# fastkey_-_v1.net
KiCad netlist of a schematic drawn in EAGLE
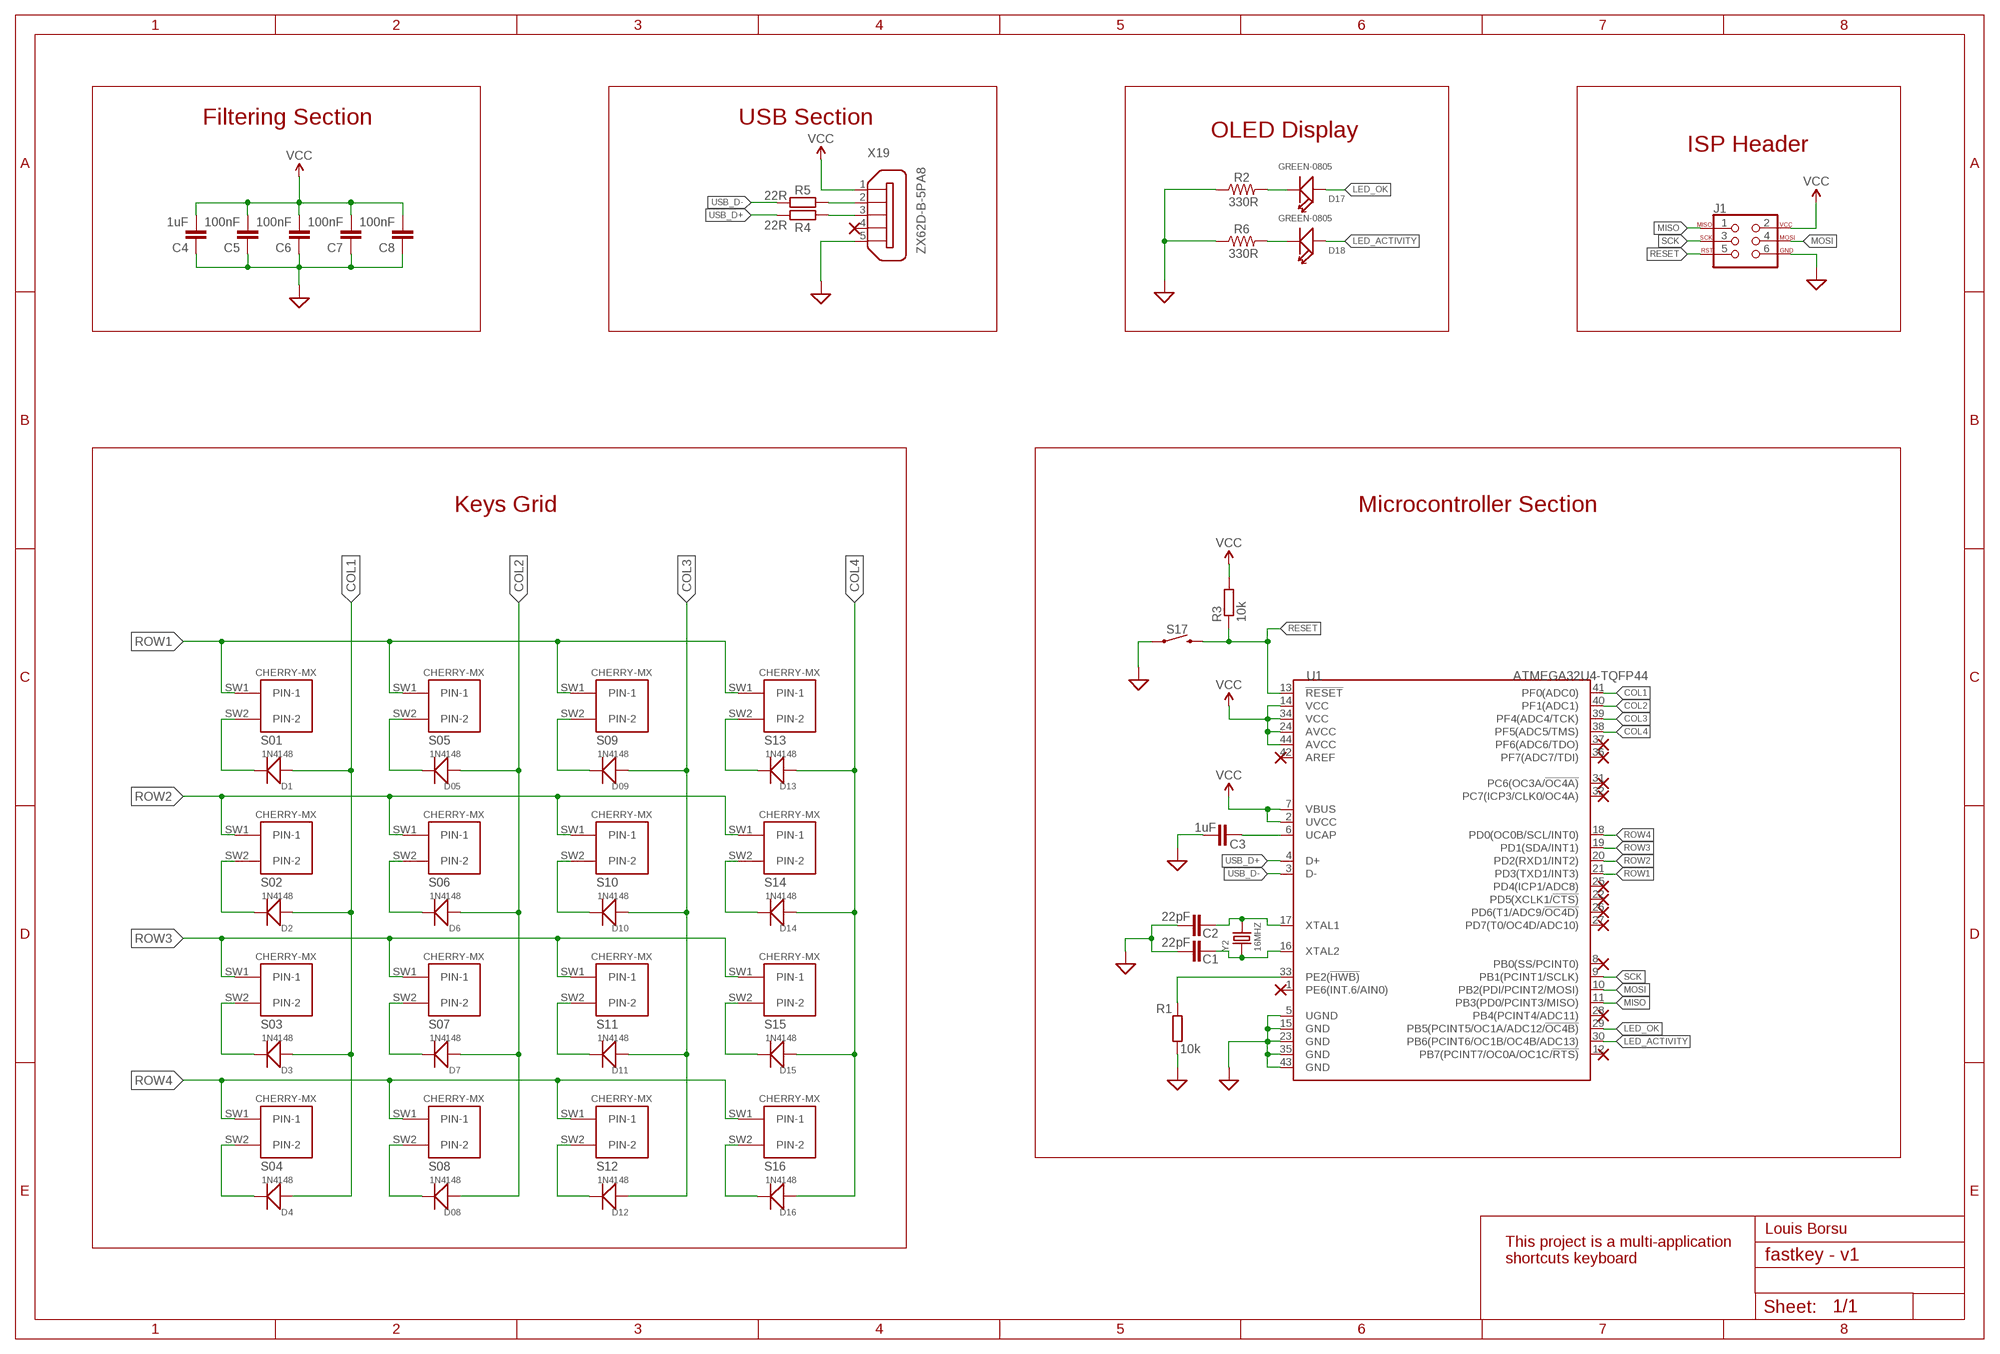
[diagram p0: schematic, sheet 1]

(export (version "E")
  (design (tool "Eeschema 10.0.6"))
  (components
    (comp (ref "C1")
      (value "22pF")
      (footprint "eagle-import:RESC0805_M")
      (libsource (lib "eagle-import") (part "CAPACITOR_0805_M"))
    )
    (comp (ref "C2")
      (value "22pF")
      (footprint "eagle-import:RESC0805_M")
      (libsource (lib "eagle-import") (part "CAPACITOR_0805_M"))
    )
    (comp (ref "C3")
      (value "1uF")
      (footprint "eagle-import:RESC0805_M")
      (libsource (lib "eagle-import") (part "CAPACITOR_0805_M"))
    )
    (comp (ref "C4")
      (value "1uF")
      (footprint "eagle-import:RESC0805_M")
      (libsource (lib "eagle-import") (part "CAPACITOR_0805_M"))
    )
    (comp (ref "C5")
      (value "100nF")
      (footprint "eagle-import:RESC0805_M")
      (libsource (lib "eagle-import") (part "CAPACITOR_0805_M"))
    )
    (comp (ref "C6")
      (value "100nF")
      (footprint "eagle-import:RESC0805_M")
      (libsource (lib "eagle-import") (part "CAPACITOR_0805_M"))
    )
    (comp (ref "C7")
      (value "100nF")
      (footprint "eagle-import:RESC0805_M")
      (libsource (lib "eagle-import") (part "CAPACITOR_0805_M"))
    )
    (comp (ref "C8")
      (value "100nF")
      (footprint "eagle-import:RESC0805_M")
      (libsource (lib "eagle-import") (part "CAPACITOR_0805_M"))
    )
    (comp (ref "D1")
      (value "1N4148")
      (footprint "eagle-import:LL-34")
      (libsource (lib "eagle-import") (part "SMD-DIODE-SWITCH-1N4148(LL-34)"))
    )
    (comp (ref "D2")
      (value "1N4148")
      (footprint "eagle-import:LL-34")
      (libsource (lib "eagle-import") (part "SMD-DIODE-SWITCH-1N4148(LL-34)"))
    )
    (comp (ref "D3")
      (value "1N4148")
      (footprint "eagle-import:LL-34")
      (libsource (lib "eagle-import") (part "SMD-DIODE-SWITCH-1N4148(LL-34)"))
    )
    (comp (ref "D4")
      (value "1N4148")
      (footprint "eagle-import:LL-34")
      (libsource (lib "eagle-import") (part "SMD-DIODE-SWITCH-1N4148(LL-34)"))
    )
    (comp (ref "D05")
      (value "1N4148")
      (footprint "eagle-import:LL-34")
      (libsource (lib "eagle-import") (part "SMD-DIODE-SWITCH-1N4148(LL-34)"))
    )
    (comp (ref "D6")
      (value "1N4148")
      (footprint "eagle-import:LL-34")
      (libsource (lib "eagle-import") (part "SMD-DIODE-SWITCH-1N4148(LL-34)"))
    )
    (comp (ref "D7")
      (value "1N4148")
      (footprint "eagle-import:LL-34")
      (libsource (lib "eagle-import") (part "SMD-DIODE-SWITCH-1N4148(LL-34)"))
    )
    (comp (ref "D08")
      (value "1N4148")
      (footprint "eagle-import:LL-34")
      (libsource (lib "eagle-import") (part "SMD-DIODE-SWITCH-1N4148(LL-34)"))
    )
    (comp (ref "D09")
      (value "1N4148")
      (footprint "eagle-import:LL-34")
      (libsource (lib "eagle-import") (part "SMD-DIODE-SWITCH-1N4148(LL-34)"))
    )
    (comp (ref "D10")
      (value "1N4148")
      (footprint "eagle-import:LL-34")
      (libsource (lib "eagle-import") (part "SMD-DIODE-SWITCH-1N4148(LL-34)"))
    )
    (comp (ref "D11")
      (value "1N4148")
      (footprint "eagle-import:LL-34")
      (libsource (lib "eagle-import") (part "SMD-DIODE-SWITCH-1N4148(LL-34)"))
    )
    (comp (ref "D12")
      (value "1N4148")
      (footprint "eagle-import:LL-34")
      (libsource (lib "eagle-import") (part "SMD-DIODE-SWITCH-1N4148(LL-34)"))
    )
    (comp (ref "D13")
      (value "1N4148")
      (footprint "eagle-import:LL-34")
      (libsource (lib "eagle-import") (part "SMD-DIODE-SWITCH-1N4148(LL-34)"))
    )
    (comp (ref "D14")
      (value "1N4148")
      (footprint "eagle-import:LL-34")
      (libsource (lib "eagle-import") (part "SMD-DIODE-SWITCH-1N4148(LL-34)"))
    )
    (comp (ref "D15")
      (value "1N4148")
      (footprint "eagle-import:LL-34")
      (libsource (lib "eagle-import") (part "SMD-DIODE-SWITCH-1N4148(LL-34)"))
    )
    (comp (ref "D16")
      (value "1N4148")
      (footprint "eagle-import:LL-34")
      (libsource (lib "eagle-import") (part "SMD-DIODE-SWITCH-1N4148(LL-34)"))
    )
    (comp (ref "D17")
      (value "GREEN-0805")
      (footprint "eagle-import:LED-0805")
      (fields (field (name "MPN") "17-215SYGC/S530-E2/TR8"))
      (libsource (lib "eagle-import") (part "SMD-LED-CLEAR-GREEN(0805)"))
    )
    (comp (ref "D18")
      (value "GREEN-0805")
      (footprint "eagle-import:LED-0805")
      (fields (field (name "MPN") "17-215SYGC/S530-E2/TR8"))
      (libsource (lib "eagle-import") (part "SMD-LED-CLEAR-GREEN(0805)"))
    )
    (comp (ref "J1")
      (value "AVR_SPI_PROG_3X22X3_LOCK")
      (footprint "eagle-import:2X3_LOCK")
      (libsource (lib "eagle-import") (part "AVR_SPI_PROG_3X22X3_LOCK"))
    )
    (comp (ref "R1")
      (value "10k")
      (footprint "eagle-import:R0805")
      (libsource (lib "eagle-import") (part "R-EU_R0805"))
    )
    (comp (ref "R2")
      (value "330R")
      (footprint "eagle-import:0805")
      (libsource (lib "eagle-import") (part "RESISTOR0805"))
    )
    (comp (ref "R3")
      (value "10k")
      (footprint "eagle-import:R0805")
      (libsource (lib "eagle-import") (part "R-EU_R0805"))
    )
    (comp (ref "R4")
      (value "22R")
      (footprint "eagle-import:R0805")
      (libsource (lib "eagle-import") (part "R-EU_R0805"))
    )
    (comp (ref "R5")
      (value "22R")
      (footprint "eagle-import:R0805")
      (libsource (lib "eagle-import") (part "R-EU_R0805"))
    )
    (comp (ref "R6")
      (value "330R")
      (footprint "eagle-import:0805")
      (libsource (lib "eagle-import") (part "RESISTOR0805"))
    )
    (comp (ref "S01")
      (value "CHERRY-MX")
      (footprint "eagle-import:CHERRY-MX")
      (libsource (lib "eagle-import") (part "CHERRY-MX"))
    )
    (comp (ref "S02")
      (value "CHERRY-MX")
      (footprint "eagle-import:CHERRY-MX")
      (libsource (lib "eagle-import") (part "CHERRY-MX"))
    )
    (comp (ref "S03")
      (value "CHERRY-MX")
      (footprint "eagle-import:CHERRY-MX")
      (libsource (lib "eagle-import") (part "CHERRY-MX"))
    )
    (comp (ref "S04")
      (value "CHERRY-MX")
      (footprint "eagle-import:CHERRY-MX")
      (libsource (lib "eagle-import") (part "CHERRY-MX"))
    )
    (comp (ref "S05")
      (value "CHERRY-MX")
      (footprint "eagle-import:CHERRY-MX")
      (libsource (lib "eagle-import") (part "CHERRY-MX"))
    )
    (comp (ref "S06")
      (value "CHERRY-MX")
      (footprint "eagle-import:CHERRY-MX")
      (libsource (lib "eagle-import") (part "CHERRY-MX"))
    )
    (comp (ref "S07")
      (value "CHERRY-MX")
      (footprint "eagle-import:CHERRY-MX")
      (libsource (lib "eagle-import") (part "CHERRY-MX"))
    )
    (comp (ref "S08")
      (value "CHERRY-MX")
      (footprint "eagle-import:CHERRY-MX")
      (libsource (lib "eagle-import") (part "CHERRY-MX"))
    )
    (comp (ref "S09")
      (value "CHERRY-MX")
      (footprint "eagle-import:CHERRY-MX")
      (libsource (lib "eagle-import") (part "CHERRY-MX"))
    )
    (comp (ref "S10")
      (value "CHERRY-MX")
      (footprint "eagle-import:CHERRY-MX")
      (libsource (lib "eagle-import") (part "CHERRY-MX"))
    )
    (comp (ref "S11")
      (value "CHERRY-MX")
      (footprint "eagle-import:CHERRY-MX")
      (libsource (lib "eagle-import") (part "CHERRY-MX"))
    )
    (comp (ref "S12")
      (value "CHERRY-MX")
      (footprint "eagle-import:CHERRY-MX")
      (libsource (lib "eagle-import") (part "CHERRY-MX"))
    )
    (comp (ref "S13")
      (value "CHERRY-MX")
      (footprint "eagle-import:CHERRY-MX")
      (libsource (lib "eagle-import") (part "CHERRY-MX"))
    )
    (comp (ref "S14")
      (value "CHERRY-MX")
      (footprint "eagle-import:CHERRY-MX")
      (libsource (lib "eagle-import") (part "CHERRY-MX"))
    )
    (comp (ref "S15")
      (value "CHERRY-MX")
      (footprint "eagle-import:CHERRY-MX")
      (libsource (lib "eagle-import") (part "CHERRY-MX"))
    )
    (comp (ref "S16")
      (value "CHERRY-MX")
      (footprint "eagle-import:CHERRY-MX")
      (libsource (lib "eagle-import") (part "CHERRY-MX"))
    )
    (comp (ref "S17")
      (value "MOMENTARY-SWITCH-SPST-SMD-6.2MM-TALL")
      (footprint "eagle-import:TACTILE_SWITCH_SMD_6.2MM_TALL")
      (libsource (lib "eagle-import") (part "MOMENTARY-SWITCH-SPST-SMD-6.2MM-TALL"))
    )
    (comp (ref "U1")
      (value "ATMEGA32U4-TQFP44")
      (footprint "eagle-import:TQFP44-0.8-9.6X9.6MM")
      (fields (field (name "MPN") "ATMEGA32U4"))
      (libsource (lib "eagle-import") (part "MCU-ATMEGA32U4-AU(TQFP44)"))
    )
    (comp (ref "X19")
      (value "ZX62D-B-5PA8")
      (footprint "eagle-import:ZX62D-B-5PA8")
      (fields (field (name "MF") "Hirose"))
      (libsource (lib "eagle-import") (part "ZX62D-B-5PA8"))
    )
    (comp (ref "Y2")
      (value "16MHZ")
      (footprint "eagle-import:X2-SMD-5.0X3.2X1.3MM")
      (fields (field (name "MPN") "X053201602002"))
      (libsource (lib "eagle-import") (part "SMD-CRYSTAL-16MHZ-8PF-20PPM-40R(2P-5.0X3.2MM)"))
    )
  )
  (nets
    (net (code "1") (name "COL1") (class "Default")
      (node (ref "D1") (pin "A") (pinfunction "+_A") (pintype "passive"))
      (node (ref "D2") (pin "A") (pinfunction "+_A") (pintype "passive"))
      (node (ref "D3") (pin "A") (pinfunction "+_A") (pintype "passive"))
      (node (ref "D4") (pin "A") (pinfunction "+_A") (pintype "passive"))
      (node (ref "U1") (pin "41") (pinfunction "PF0(ADC0)_41") (pintype "bidirectional"))
    )
    (net (code "2") (name "COL2") (class "Default")
      (node (ref "D05") (pin "A") (pinfunction "+_A") (pintype "passive"))
      (node (ref "D08") (pin "A") (pinfunction "+_A") (pintype "passive"))
      (node (ref "D6") (pin "A") (pinfunction "+_A") (pintype "passive"))
      (node (ref "D7") (pin "A") (pinfunction "+_A") (pintype "passive"))
      (node (ref "U1") (pin "40") (pinfunction "PF1(ADC1)_40") (pintype "bidirectional"))
    )
    (net (code "3") (name "COL3") (class "Default")
      (node (ref "D09") (pin "A") (pinfunction "+_A") (pintype "passive"))
      (node (ref "D10") (pin "A") (pinfunction "+_A") (pintype "passive"))
      (node (ref "D11") (pin "A") (pinfunction "+_A") (pintype "passive"))
      (node (ref "D12") (pin "A") (pinfunction "+_A") (pintype "passive"))
      (node (ref "U1") (pin "39") (pinfunction "PF4(ADC4/TCK)_39") (pintype "bidirectional"))
    )
    (net (code "4") (name "COL4") (class "Default")
      (node (ref "D13") (pin "A") (pinfunction "+_A") (pintype "passive"))
      (node (ref "D14") (pin "A") (pinfunction "+_A") (pintype "passive"))
      (node (ref "D15") (pin "A") (pinfunction "+_A") (pintype "passive"))
      (node (ref "D16") (pin "A") (pinfunction "+_A") (pintype "passive"))
      (node (ref "U1") (pin "38") (pinfunction "PF5(ADC5/TMS)_38") (pintype "bidirectional"))
    )
    (net (code "5") (name "LED_ACTIVITY") (class "Default")
      (node (ref "D18") (pin "+") (pinfunction "+_+") (pintype "passive"))
      (node (ref "U1") (pin "30") (pinfunction "PB6(PCINT6/OC1B/OC4B/ADC13)_30") (pintype "bidirectional"))
    )
    (net (code "6") (name "LED_OK") (class "Default")
      (node (ref "D17") (pin "+") (pinfunction "+_+") (pintype "passive"))
      (node (ref "U1") (pin "29") (pinfunction "PB5(PCINT5/OC1A/ADC12/~{OC4B})_29") (pintype "bidirectional"))
    )
    (net (code "7") (name "MISO") (class "Default")
      (node (ref "J1") (pin "1") (pinfunction "1_1") (pintype "passive"))
      (node (ref "U1") (pin "11") (pinfunction "PB3(PD0/PCINT3/MISO)_11") (pintype "bidirectional"))
    )
    (net (code "8") (name "MOSI") (class "Default")
      (node (ref "J1") (pin "4") (pinfunction "4_4") (pintype "passive"))
      (node (ref "U1") (pin "10") (pinfunction "PB2(PDI/PCINT2/MOSI)_10") (pintype "bidirectional"))
    )
    (net (code "9") (name "Net-(D1--)") (class "Default")
      (node (ref "D1") (pin "C") (pinfunction "-_C") (pintype "passive"))
      (node (ref "S01") (pin "SW2") (pinfunction "PIN-2_SW2") (pintype "bidirectional"))
    )
    (net (code "10") (name "Net-(D2--)") (class "Default")
      (node (ref "D2") (pin "C") (pinfunction "-_C") (pintype "passive"))
      (node (ref "S02") (pin "SW2") (pinfunction "PIN-2_SW2") (pintype "bidirectional"))
    )
    (net (code "11") (name "Net-(D3--)") (class "Default")
      (node (ref "D3") (pin "C") (pinfunction "-_C") (pintype "passive"))
      (node (ref "S03") (pin "SW2") (pinfunction "PIN-2_SW2") (pintype "bidirectional"))
    )
    (net (code "12") (name "Net-(D4--)") (class "Default")
      (node (ref "D4") (pin "C") (pinfunction "-_C") (pintype "passive"))
      (node (ref "S04") (pin "SW2") (pinfunction "PIN-2_SW2") (pintype "bidirectional"))
    )
    (net (code "13") (name "Net-(D05--)") (class "Default")
      (node (ref "D05") (pin "C") (pinfunction "-_C") (pintype "passive"))
      (node (ref "S05") (pin "SW2") (pinfunction "PIN-2_SW2") (pintype "bidirectional"))
    )
    (net (code "14") (name "Net-(D6--)") (class "Default")
      (node (ref "D6") (pin "C") (pinfunction "-_C") (pintype "passive"))
      (node (ref "S06") (pin "SW2") (pinfunction "PIN-2_SW2") (pintype "bidirectional"))
    )
    (net (code "15") (name "Net-(D7--)") (class "Default")
      (node (ref "D7") (pin "C") (pinfunction "-_C") (pintype "passive"))
      (node (ref "S07") (pin "SW2") (pinfunction "PIN-2_SW2") (pintype "bidirectional"))
    )
    (net (code "16") (name "Net-(D08--)") (class "Default")
      (node (ref "D08") (pin "C") (pinfunction "-_C") (pintype "passive"))
      (node (ref "S08") (pin "SW2") (pinfunction "PIN-2_SW2") (pintype "bidirectional"))
    )
    (net (code "17") (name "Net-(D09--)") (class "Default")
      (node (ref "D09") (pin "C") (pinfunction "-_C") (pintype "passive"))
      (node (ref "S09") (pin "SW2") (pinfunction "PIN-2_SW2") (pintype "bidirectional"))
    )
    (net (code "18") (name "Net-(D10--)") (class "Default")
      (node (ref "D10") (pin "C") (pinfunction "-_C") (pintype "passive"))
      (node (ref "S10") (pin "SW2") (pinfunction "PIN-2_SW2") (pintype "bidirectional"))
    )
    (net (code "19") (name "Net-(D11--)") (class "Default")
      (node (ref "D11") (pin "C") (pinfunction "-_C") (pintype "passive"))
      (node (ref "S11") (pin "SW2") (pinfunction "PIN-2_SW2") (pintype "bidirectional"))
    )
    (net (code "20") (name "Net-(D12--)") (class "Default")
      (node (ref "D12") (pin "C") (pinfunction "-_C") (pintype "passive"))
      (node (ref "S12") (pin "SW2") (pinfunction "PIN-2_SW2") (pintype "bidirectional"))
    )
    (net (code "21") (name "Net-(D13--)") (class "Default")
      (node (ref "D13") (pin "C") (pinfunction "-_C") (pintype "passive"))
      (node (ref "S13") (pin "SW2") (pinfunction "PIN-2_SW2") (pintype "bidirectional"))
    )
    (net (code "22") (name "Net-(D14--)") (class "Default")
      (node (ref "D14") (pin "C") (pinfunction "-_C") (pintype "passive"))
      (node (ref "S14") (pin "SW2") (pinfunction "PIN-2_SW2") (pintype "bidirectional"))
    )
    (net (code "23") (name "Net-(D15--)") (class "Default")
      (node (ref "D15") (pin "C") (pinfunction "-_C") (pintype "passive"))
      (node (ref "S15") (pin "SW2") (pinfunction "PIN-2_SW2") (pintype "bidirectional"))
    )
    (net (code "24") (name "Net-(D16--)") (class "Default")
      (node (ref "D16") (pin "C") (pinfunction "-_C") (pintype "passive"))
      (node (ref "S16") (pin "SW2") (pinfunction "PIN-2_SW2") (pintype "bidirectional"))
    )
    (net (code "25") (name "Net-(D17-Pad-)") (class "Default")
      (node (ref "D17") (pin "-") (pinfunction "-_-") (pintype "passive"))
      (node (ref "R2") (pin "2") (pinfunction "2_2") (pintype "passive"))
    )
    (net (code "26") (name "Net-(D18-Pad-)") (class "Default")
      (node (ref "D18") (pin "-") (pinfunction "-_-") (pintype "passive"))
      (node (ref "R6") (pin "2") (pinfunction "2_2") (pintype "passive"))
    )
    (net (code "27") (name "Net-(R4-Pad1)") (class "Default")
      (node (ref "R4") (pin "1") (pinfunction "1_1") (pintype "passive"))
      (node (ref "X19") (pin "3") (pinfunction "3_3") (pintype "passive"))
    )
    (net (code "28") (name "Net-(R5-Pad1)") (class "Default")
      (node (ref "R5") (pin "1") (pinfunction "1_1") (pintype "passive"))
      (node (ref "X19") (pin "2") (pinfunction "2_2") (pintype "passive"))
    )
    (net (code "29") (name "Net-(U1-PE2(~{HWB}))") (class "Default")
      (node (ref "R1") (pin "2") (pinfunction "2_2") (pintype "passive"))
      (node (ref "U1") (pin "33") (pinfunction "PE2(~{HWB})_33") (pintype "bidirectional"))
    )
    (net (code "30") (name "Net-(U1-UCAP)") (class "Default")
      (node (ref "C3") (pin "2") (pinfunction "2_2") (pintype "passive"))
      (node (ref "U1") (pin "6") (pinfunction "UCAP_6") (pintype "bidirectional"))
    )
    (net (code "31") (name "Net-(U1-XTAL1)") (class "Default")
      (node (ref "C2") (pin "2") (pinfunction "2_2") (pintype "passive"))
      (node (ref "U1") (pin "17") (pinfunction "XTAL1_17") (pintype "bidirectional"))
      (node (ref "Y2") (pin "2") (pinfunction "2_2") (pintype "passive"))
    )
    (net (code "32") (name "Net-(U1-XTAL2)") (class "Default")
      (node (ref "C1") (pin "2") (pinfunction "2_2") (pintype "passive"))
      (node (ref "U1") (pin "16") (pinfunction "XTAL2_16") (pintype "bidirectional"))
      (node (ref "Y2") (pin "1") (pinfunction "1_1") (pintype "passive"))
    )
    (net (code "33") (name "RESET") (class "Default")
      (node (ref "J1") (pin "5") (pinfunction "5_5") (pintype "passive"))
      (node (ref "R3") (pin "1") (pinfunction "1_1") (pintype "passive"))
      (node (ref "S17") (pin "B2") (pinfunction "2_B2") (pintype "passive"))
      (node (ref "U1") (pin "13") (pinfunction "~{RESET}_13") (pintype "bidirectional"))
    )
    (net (code "34") (name "ROW1") (class "Default")
      (node (ref "S01") (pin "SW1") (pinfunction "PIN-1_SW1") (pintype "bidirectional"))
      (node (ref "S05") (pin "SW1") (pinfunction "PIN-1_SW1") (pintype "bidirectional"))
      (node (ref "S09") (pin "SW1") (pinfunction "PIN-1_SW1") (pintype "bidirectional"))
      (node (ref "S13") (pin "SW1") (pinfunction "PIN-1_SW1") (pintype "bidirectional"))
      (node (ref "U1") (pin "21") (pinfunction "PD3(TXD1/INT3)_21") (pintype "bidirectional"))
    )
    (net (code "35") (name "ROW2") (class "Default")
      (node (ref "S02") (pin "SW1") (pinfunction "PIN-1_SW1") (pintype "bidirectional"))
      (node (ref "S06") (pin "SW1") (pinfunction "PIN-1_SW1") (pintype "bidirectional"))
      (node (ref "S10") (pin "SW1") (pinfunction "PIN-1_SW1") (pintype "bidirectional"))
      (node (ref "S14") (pin "SW1") (pinfunction "PIN-1_SW1") (pintype "bidirectional"))
      (node (ref "U1") (pin "20") (pinfunction "PD2(RXD1/INT2)_20") (pintype "bidirectional"))
    )
    (net (code "36") (name "ROW3") (class "Default")
      (node (ref "S03") (pin "SW1") (pinfunction "PIN-1_SW1") (pintype "bidirectional"))
      (node (ref "S07") (pin "SW1") (pinfunction "PIN-1_SW1") (pintype "bidirectional"))
      (node (ref "S11") (pin "SW1") (pinfunction "PIN-1_SW1") (pintype "bidirectional"))
      (node (ref "S15") (pin "SW1") (pinfunction "PIN-1_SW1") (pintype "bidirectional"))
      (node (ref "U1") (pin "19") (pinfunction "PD1(SDA/INT1)_19") (pintype "bidirectional"))
    )
    (net (code "37") (name "ROW4") (class "Default")
      (node (ref "S04") (pin "SW1") (pinfunction "PIN-1_SW1") (pintype "bidirectional"))
      (node (ref "S08") (pin "SW1") (pinfunction "PIN-1_SW1") (pintype "bidirectional"))
      (node (ref "S12") (pin "SW1") (pinfunction "PIN-1_SW1") (pintype "bidirectional"))
      (node (ref "S16") (pin "SW1") (pinfunction "PIN-1_SW1") (pintype "bidirectional"))
      (node (ref "U1") (pin "18") (pinfunction "PD0(OC0B/SCL/INT0)_18") (pintype "bidirectional"))
    )
    (net (code "38") (name "SCK") (class "Default")
      (node (ref "J1") (pin "3") (pinfunction "3_3") (pintype "passive"))
      (node (ref "U1") (pin "9") (pinfunction "PB1(PCINT1/SCLK)_9") (pintype "bidirectional"))
    )
    (net (code "39") (name "SUP") (class "Default")
      (node (ref "C1") (pin "1") (pinfunction "1_1") (pintype "passive"))
      (node (ref "C2") (pin "1") (pinfunction "1_1") (pintype "passive"))
      (node (ref "C3") (pin "1") (pinfunction "1_1") (pintype "passive"))
      (node (ref "C4") (pin "1") (pinfunction "1_1") (pintype "passive"))
      (node (ref "C5") (pin "1") (pinfunction "1_1") (pintype "passive"))
      (node (ref "C6") (pin "1") (pinfunction "1_1") (pintype "passive"))
      (node (ref "C7") (pin "1") (pinfunction "1_1") (pintype "passive"))
      (node (ref "C8") (pin "1") (pinfunction "1_1") (pintype "passive"))
      (node (ref "J1") (pin "6") (pinfunction "6_6") (pintype "passive"))
      (node (ref "R1") (pin "1") (pinfunction "1_1") (pintype "passive"))
      (node (ref "R2") (pin "1") (pinfunction "1_1") (pintype "passive"))
      (node (ref "R6") (pin "1") (pinfunction "1_1") (pintype "passive"))
      (node (ref "S17") (pin "A2") (pinfunction "1_A2") (pintype "passive"))
      (node (ref "U1") (pin "15") (pinfunction "GND_15") (pintype "bidirectional"))
      (node (ref "U1") (pin "23") (pinfunction "GND_23") (pintype "bidirectional"))
      (node (ref "U1") (pin "35") (pinfunction "GND_35") (pintype "bidirectional"))
      (node (ref "U1") (pin "43") (pinfunction "GND_43") (pintype "bidirectional"))
      (node (ref "U1") (pin "5") (pinfunction "UGND_5") (pintype "bidirectional"))
      (node (ref "X19") (pin "5") (pinfunction "5_5") (pintype "passive"))
    )
    (net (code "40") (name "USB_D+") (class "Default")
      (node (ref "R4") (pin "2") (pinfunction "2_2") (pintype "passive"))
      (node (ref "U1") (pin "4") (pinfunction "D+_4") (pintype "bidirectional"))
    )
    (net (code "41") (name "USB_D-") (class "Default")
      (node (ref "R5") (pin "2") (pinfunction "2_2") (pintype "passive"))
      (node (ref "U1") (pin "3") (pinfunction "D-_3") (pintype "bidirectional"))
    )
    (net (code "42") (name "VCC") (class "Default")
      (node (ref "C4") (pin "2") (pinfunction "2_2") (pintype "passive"))
      (node (ref "C5") (pin "2") (pinfunction "2_2") (pintype "passive"))
      (node (ref "C6") (pin "2") (pinfunction "2_2") (pintype "passive"))
      (node (ref "C7") (pin "2") (pinfunction "2_2") (pintype "passive"))
      (node (ref "C8") (pin "2") (pinfunction "2_2") (pintype "passive"))
      (node (ref "J1") (pin "2") (pinfunction "2_2") (pintype "passive"))
      (node (ref "R3") (pin "2") (pinfunction "2_2") (pintype "passive"))
      (node (ref "U1") (pin "14") (pinfunction "VCC_14") (pintype "bidirectional"))
      (node (ref "U1") (pin "2") (pinfunction "UVCC_2") (pintype "bidirectional"))
      (node (ref "U1") (pin "24") (pinfunction "AVCC_24") (pintype "bidirectional"))
      (node (ref "U1") (pin "34") (pinfunction "VCC_34") (pintype "bidirectional"))
      (node (ref "U1") (pin "44") (pinfunction "AVCC_44") (pintype "bidirectional"))
      (node (ref "U1") (pin "7") (pinfunction "VBUS_7") (pintype "bidirectional"))
      (node (ref "X19") (pin "1") (pinfunction "1_1") (pintype "passive"))
    )
    (net (code "43") (name "unconnected-(U1-AREF-Pad42)") (class "Default")
      (node (ref "U1") (pin "42") (pinfunction "AREF_42") (pintype "bidirectional"))
    )
    (net (code "44") (name "unconnected-(U1-PB0(SS{slash}PCINT0)-Pad8)") (class "Default")
      (node (ref "U1") (pin "8") (pinfunction "PB0(SS/PCINT0)_8") (pintype "bidirectional"))
    )
    (net (code "45") (name "unconnected-(U1-PB4(PCINT4{slash}ADC11)-Pad28)") (class "Default")
      (node (ref "U1") (pin "28") (pinfunction "PB4(PCINT4/ADC11)_28") (pintype "bidirectional"))
    )
    (net (code "46") (name "unconnected-(U1-PB7(PCINT7{slash}OC0A{slash}OC1C{slash}~{RTS})-Pad12)") (class "Default")
      (node (ref "U1") (pin "12") (pinfunction "PB7(PCINT7/OC0A/OC1C/~{RTS})_12") (pintype "bidirectional"))
    )
    (net (code "47") (name "unconnected-(U1-PC6(OC3A{slash}~{OC4A})-Pad31)") (class "Default")
      (node (ref "U1") (pin "31") (pinfunction "PC6(OC3A/~{OC4A})_31") (pintype "bidirectional"))
    )
    (net (code "48") (name "unconnected-(U1-PC7(ICP3{slash}CLK0{slash}OC4A)-Pad32)") (class "Default")
      (node (ref "U1") (pin "32") (pinfunction "PC7(ICP3/CLK0/OC4A)_32") (pintype "bidirectional"))
    )
    (net (code "49") (name "unconnected-(U1-PD4(ICP1{slash}ADC8)-Pad25)") (class "Default")
      (node (ref "U1") (pin "25") (pinfunction "PD4(ICP1/ADC8)_25") (pintype "bidirectional"))
    )
    (net (code "50") (name "unconnected-(U1-PD5(XCLK1{slash}~{CTS})-Pad22)") (class "Default")
      (node (ref "U1") (pin "22") (pinfunction "PD5(XCLK1/~{CTS})_22") (pintype "bidirectional"))
    )
    (net (code "51") (name "unconnected-(U1-PD6(T1{slash}ADC9{slash}~{OC4D})-Pad26)") (class "Default")
      (node (ref "U1") (pin "26") (pinfunction "PD6(T1/ADC9/~{OC4D})_26") (pintype "bidirectional"))
    )
    (net (code "52") (name "unconnected-(U1-PD7(T0{slash}OC4D{slash}ADC10)-Pad27)") (class "Default")
      (node (ref "U1") (pin "27") (pinfunction "PD7(T0/OC4D/ADC10)_27") (pintype "bidirectional"))
    )
    (net (code "53") (name "unconnected-(U1-PE6(INT.6{slash}AIN0)-Pad1)") (class "Default")
      (node (ref "U1") (pin "1") (pinfunction "PE6(INT.6/AIN0)_1") (pintype "bidirectional"))
    )
    (net (code "54") (name "unconnected-(U1-PF6(ADC6{slash}TDO)-Pad37)") (class "Default")
      (node (ref "U1") (pin "37") (pinfunction "PF6(ADC6/TDO)_37") (pintype "bidirectional"))
    )
    (net (code "55") (name "unconnected-(U1-PF7(ADC7{slash}TDI)-Pad36)") (class "Default")
      (node (ref "U1") (pin "36") (pinfunction "PF7(ADC7/TDI)_36") (pintype "bidirectional"))
    )
    (net (code "56") (name "unconnected-(X19-Pad4)") (class "Default")
      (node (ref "X19") (pin "4") (pinfunction "4_4") (pintype "passive"))
    )
  )
)
